# FTDI.net
KiCad netlist of a schematic drawn in Altium Designer
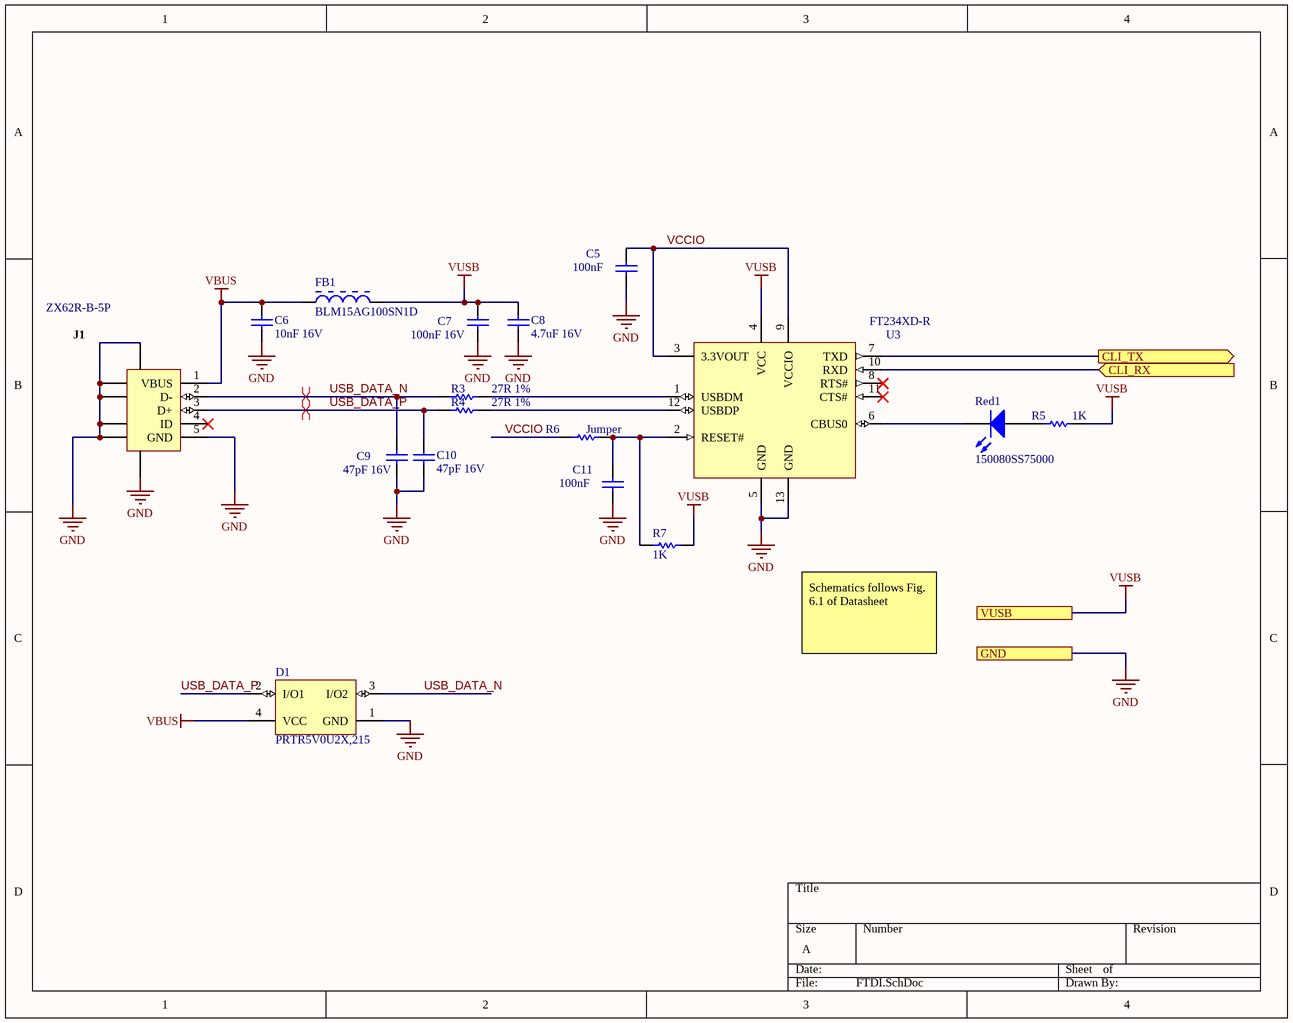
[diagram p0: FTDI.SchDoc]

(export (version "E")
  (design (tool "Eeschema 10.0.6"))
  (components
    (comp (ref "C5")
      (value "100nF")
      (footprint "CAPC0402(1005)60_N")
      (description "CAP 100nF 6.3V ±20% 0402 (1005 Metric) Thickness 0.6mm SMD")
      (fields (field (name "TOLERANCE") "Â±20%"))
      (libsource (lib "Altium Content Vault") (part "CMP-1034-02062-1"))
    )
    (comp (ref "C6")
      (value "10nF 16V")
      (footprint "CAPC0603(1608)100_L")
      (description "CAP 10nF 16V ±10% 0603 (1608 Metric) Thickness 1mm SMD")
      (fields (field (name "TOLERANCE") "Â±10%"))
      (libsource (lib "Altium Content Vault") (part "CAP"))
    )
    (comp (ref "C7")
      (value "100nF 16V")
      (footprint "CAPC0603(1608)100_N")
      (description "CAP 100nF 16V ±10% 0603 (1608 Metric) Thickness 1mm SMD")
      (fields (field (name "TOLERANCE") "Â±10%"))
      (libsource (lib "Altium Content Vault") (part "CAP"))
    )
    (comp (ref "C8")
      (value "4.7uF 16V")
      (footprint "CAPC0805(2012)145_N")
      (description "CAP 4.7uF 16V ±10% 0805 (2012 Metric) Thickness 1.45mm SMD")
      (fields (field (name "TOLERANCE") "Â±10%"))
      (libsource (lib "Altium Content Vault") (part "CAP"))
    )
    (comp (ref "C9")
      (value "47pF 16V")
      (footprint "CAPC0603(1608)100_L")
      (description "CAP 47pF 16V ±0.5pF 0603 (1608 Metric) Thickness 1mm SMD")
      (fields (field (name "TOLERANCE") "Â±0.5pF"))
      (libsource (lib "Altium Content Vault") (part "CAP"))
    )
    (comp (ref "C10")
      (value "47pF 16V")
      (footprint "CAPC0603(1608)100_L")
      (description "CAP 47pF 16V ±0.5pF 0603 (1608 Metric) Thickness 1mm SMD")
      (fields (field (name "TOLERANCE") "Â±0.5pF"))
      (libsource (lib "Altium Content Vault") (part "CAP"))
    )
    (comp (ref "C11")
      (value "100nF")
      (footprint "CAPC0402(1005)60_N")
      (description "CAP 100nF 6.3V ±20% 0402 (1005 Metric) Thickness 0.6mm SMD")
      (fields (field (name "TOLERANCE") "Â±20%"))
      (libsource (lib "Altium Content Vault") (part "CMP-1034-02062-1"))
    )
    (comp (ref "D1")
      (value "PRTR5V0U2X,215")
      (footprint "NXP-SOT143B-4_V")
      (fields (field (name "MANUFACTURER") "NXP Semiconductors"))
      (libsource (lib "Altium Content Vault") (part "NXP-PRTR5V0U2X,215-4"))
    )
    (comp (ref "FB1")
      (value "BLM15AG100SN1D")
      (footprint "MURA-BLM15-CHIP-2_V")
      (fields (field (name "MANUFACTURER") "Murata"))
      (libsource (lib "Altium Content Vault") (part "MURA-FB-2"))
    )
    (comp (ref "J1")
      (value "ZX62R-B-5P")
      (footprint "HIRO-ZX62R-B-5P_V")
      (description "Connector; USBMicro-B,Reverse type, SMT; 5 Position; Right Angle")
      (libsource (lib "Altium Content Vault") (part "HIRO-ZX62R-B-5P-5"))
    )
    (comp (ref "R3")
      (value "27R 1%")
      (footprint "RESC0603(1608)_N")
      (description "27R 0.1W 1% 0603 (1608 Metric)  SMD")
      (fields (field (name "TOLERANCE") "1 %") (field (name "POWER") "0.1 W"))
      (libsource (lib "Altium Content Vault") (part "RES"))
    )
    (comp (ref "R4")
      (value "27R 1%")
      (footprint "RESC0603(1608)_N")
      (description "27R 0.1W 1% 0603 (1608 Metric)  SMD")
      (fields (field (name "TOLERANCE") "1 %") (field (name "POWER") "0.1 W"))
      (libsource (lib "Altium Content Vault") (part "RES"))
    )
    (comp (ref "R5")
      (value "1K")
      (footprint "RESC0603(1608)_M")
      (description "1K 0.1W 1% 0603 (1608 Metric)  SMD")
      (fields (field (name "TOLERANCE") "1 %") (field (name "POWER") "0.1 W"))
      (libsource (lib "Altium Content Vault") (part "RES"))
    )
    (comp (ref "R6")
      (value "Jumper")
      (footprint "RESC0603(1608)_N")
      (description "Jumper 0603 (1608 Metric)")
      (fields (field (name "POWER") "None"))
      (libsource (lib "Altium Content Vault") (part "RES"))
    )
    (comp (ref "R7")
      (value "1K")
      (footprint "RESC0603(1608)_M")
      (description "1K 0.1W 1% 0603 (1608 Metric)  SMD")
      (fields (field (name "TOLERANCE") "1 %") (field (name "POWER") "0.1 W"))
      (libsource (lib "Altium Content Vault") (part "RES"))
    )
    (comp (ref "Red1")
      (value "150080SS75000")
      (footprint "0805_A")
      (description "SMD mono-color Chip LED, WL-SMCW, Super Red")
      (fields (field (name "MANUFACTURER") "Wuerth Elektronik"))
      (libsource (lib "Altium Content Vault") (part "WE-LED_K1A2-2"))
    )
    (comp (ref "U3")
      (value "FT234XD-R")
      (footprint "DFN-12_V")
      (description "FT234XD USB to BASIC UART IC, -40 to +85 degC, 12-Pin DFN, Pb-Free, Tape and Reel")
      (fields (field (name "MANUFACTURER") "FTDI"))
      (libsource (lib "Altium Content Vault") (part "CMP-0248-00027-1"))
    )
  )
  (nets
    (net (code "1") (name "/CLI_RX") (class "Default")
      (node (ref "U3") (pin "10") (pinfunction "RXD_10") (pintype "input"))
    )
    (net (code "2") (name "/CLI_TX") (class "Default")
      (node (ref "U3") (pin "7") (pinfunction "TXD_7") (pintype "output"))
    )
    (net (code "3") (name "/USB_DATA_N") (class "Default")
      (node (ref "C9") (pin "2") (pinfunction "2_2") (pintype "passive"))
      (node (ref "D1") (pin "3") (pinfunction "I/O2_3") (pintype "bidirectional"))
      (node (ref "J1") (pin "2") (pinfunction "D-_2") (pintype "bidirectional"))
      (node (ref "R3") (pin "1") (pinfunction "1_1") (pintype "passive"))
    )
    (net (code "4") (name "/USB_DATA_P") (class "Default")
      (node (ref "C10") (pin "2") (pinfunction "2_2") (pintype "passive"))
      (node (ref "D1") (pin "2") (pinfunction "I/O1_2") (pintype "bidirectional"))
      (node (ref "J1") (pin "3") (pinfunction "D+_3") (pintype "bidirectional"))
      (node (ref "R4") (pin "1") (pinfunction "1_1") (pintype "passive"))
    )
    (net (code "5") (name "/VCCIO") (class "Default")
      (node (ref "C5") (pin "2") (pinfunction "2_2") (pintype "passive"))
      (node (ref "R6") (pin "1") (pinfunction "1_1") (pintype "passive"))
      (node (ref "U3") (pin "3") (pinfunction "3.3VOUT_3") (pintype "power_in"))
      (node (ref "U3") (pin "9") (pinfunction "VCCIO_9") (pintype "power_in"))
    )
    (net (code "6") (name "GND") (class "Default")
      (node (ref "C10") (pin "1") (pinfunction "1_1") (pintype "passive"))
      (node (ref "C11") (pin "1") (pinfunction "1_1") (pintype "passive"))
      (node (ref "C5") (pin "1") (pinfunction "1_1") (pintype "passive"))
      (node (ref "C6") (pin "1") (pinfunction "1_1") (pintype "passive"))
      (node (ref "C7") (pin "1") (pinfunction "1_1") (pintype "passive"))
      (node (ref "C8") (pin "1") (pinfunction "1_1") (pintype "passive"))
      (node (ref "C9") (pin "1") (pinfunction "1_1") (pintype "passive"))
      (node (ref "D1") (pin "1") (pinfunction "GND_1") (pintype "power_in"))
      (node (ref "J1") (pin "10") (pinfunction "SHLD_10") (pintype "passive"))
      (node (ref "J1") (pin "11") (pinfunction "SHLD_11") (pintype "passive"))
      (node (ref "J1") (pin "5") (pinfunction "GND_5") (pintype "power_in"))
      (node (ref "J1") (pin "6") (pinfunction "SHLD_6") (pintype "passive"))
      (node (ref "J1") (pin "7") (pinfunction "SHLD_7") (pintype "passive"))
      (node (ref "J1") (pin "8") (pinfunction "SHLD_8") (pintype "passive"))
      (node (ref "J1") (pin "9") (pinfunction "SHLD_9") (pintype "passive"))
      (node (ref "U3") (pin "13") (pinfunction "GND_13") (pintype "power_in"))
      (node (ref "U3") (pin "5") (pinfunction "GND_5") (pintype "power_in"))
    )
    (net (code "7") (name "Net-(Red1-A)") (class "Default")
      (node (ref "R5") (pin "1") (pinfunction "1_1") (pintype "passive"))
      (node (ref "Red1") (pin "2") (pinfunction "A_2") (pintype "passive"))
    )
    (net (code "8") (name "Net-(Red1-K)") (class "Default")
      (node (ref "Red1") (pin "1") (pinfunction "K_1") (pintype "passive"))
      (node (ref "U3") (pin "6") (pinfunction "CBUS0_6") (pintype "bidirectional"))
    )
    (net (code "9") (name "Net-(U3-RESET#)") (class "Default")
      (node (ref "C11") (pin "2") (pinfunction "2_2") (pintype "passive"))
      (node (ref "R6") (pin "2") (pinfunction "2_2") (pintype "passive"))
      (node (ref "R7") (pin "2") (pinfunction "2_2") (pintype "passive"))
      (node (ref "U3") (pin "2") (pinfunction "RESET#_2") (pintype "input"))
    )
    (net (code "10") (name "Net-(U3-USBDM)") (class "Default")
      (node (ref "R3") (pin "2") (pinfunction "2_2") (pintype "passive"))
      (node (ref "U3") (pin "1") (pinfunction "USBDM_1") (pintype "bidirectional"))
    )
    (net (code "11") (name "Net-(U3-USBDP)") (class "Default")
      (node (ref "R4") (pin "2") (pinfunction "2_2") (pintype "passive"))
      (node (ref "U3") (pin "12") (pinfunction "USBDP_12") (pintype "bidirectional"))
    )
    (net (code "12") (name "VBUS") (class "Default")
      (node (ref "C6") (pin "2") (pinfunction "2_2") (pintype "passive"))
      (node (ref "D1") (pin "4") (pinfunction "VCC_4") (pintype "power_in"))
      (node (ref "FB1") (pin "1") (pinfunction "1_1") (pintype "passive"))
      (node (ref "J1") (pin "1") (pinfunction "VBUS_1") (pintype "power_in"))
    )
    (net (code "13") (name "VUSB") (class "Default")
      (node (ref "C7") (pin "2") (pinfunction "2_2") (pintype "passive"))
      (node (ref "C8") (pin "2") (pinfunction "2_2") (pintype "passive"))
      (node (ref "FB1") (pin "2") (pinfunction "2_2") (pintype "passive"))
      (node (ref "R5") (pin "2") (pinfunction "2_2") (pintype "passive"))
      (node (ref "R7") (pin "1") (pinfunction "1_1") (pintype "passive"))
      (node (ref "U3") (pin "4") (pinfunction "VCC_4") (pintype "power_in"))
    )
    (net (code "14") (name "unconnected-(J1-ID-Pad4)") (class "Default")
      (node (ref "J1") (pin "4") (pinfunction "ID_4") (pintype "passive+no_connect"))
    )
    (net (code "15") (name "unconnected-(U3-CTS#-Pad11)") (class "Default")
      (node (ref "U3") (pin "11") (pinfunction "CTS#_11") (pintype "input+no_connect"))
    )
    (net (code "16") (name "unconnected-(U3-RTS#-Pad8)") (class "Default")
      (node (ref "U3") (pin "8") (pinfunction "RTS#_8") (pintype "output+no_connect"))
    )
  )
)
